# Carte_Barriere_Optique_Interface.net
KiCad netlist of a schematic drawn in Altium Designer
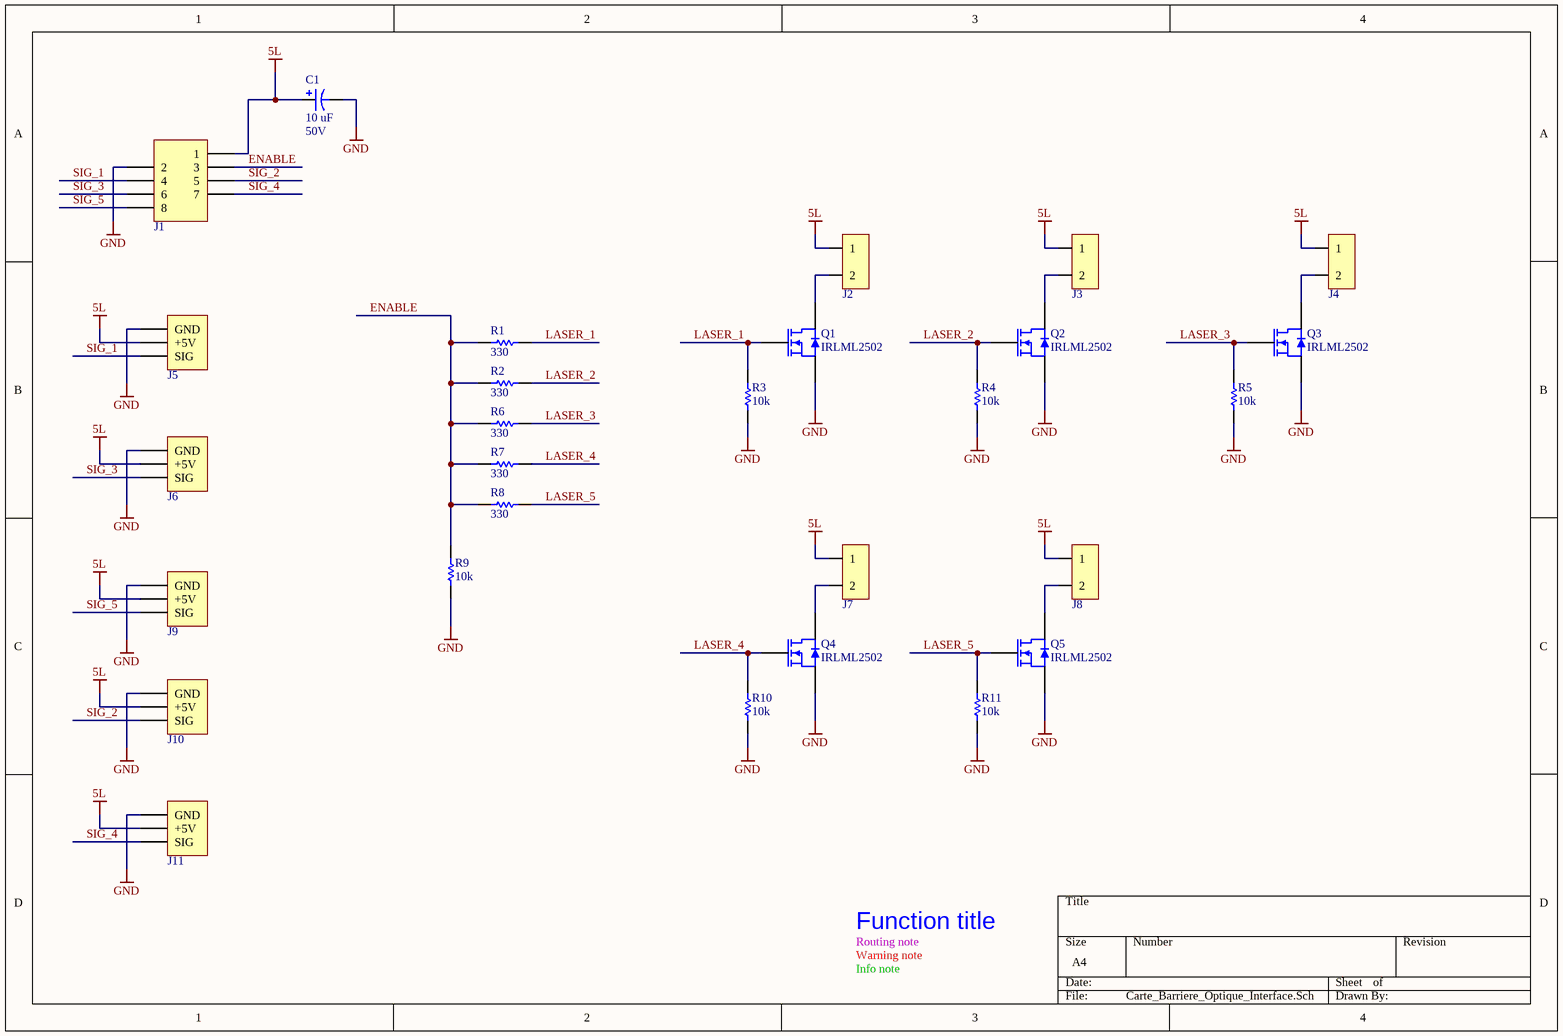
[diagram p0: Carte_Barriere_Optique_Interface.SchDoc]

(export (version "E")
  (design (tool "Eeschema 10.0.6"))
  (components
    (comp (ref "C1")
      (value "10 uF")
      (footprint "WCAP-ATG8_5x11x2x0.5")
      (description "CAP Alu 10 UF 20% 50 V")
      (fields
        (field (name "MANUFACTURER") "Wurth Elektronik")
        (field (name "MANUFACTURER PART NUMBER") "860010672009")
        (field (name "RATEDVOLTAGE") "50V")
      )
      (libsource (lib "Condensateur") (part "WCAP-ATG8, 860010672009"))
    )
    (comp (ref "J1")
      (value "690367280876")
      (footprint "690367280876")
      (description "WR-MM 8p Female SMT Connector with Polarization")
      (fields (field (name "MANUFACTURER") "Wurth Electronics Inc."))
      (libsource (lib "Connecteurs") (part "690367280876"))
    )
    (comp (ref "J2")
      (value "22-03-2021")
      (footprint "22-03-2021")
      (libsource (lib "Connecteurs") (part "22-03-2021"))
    )
    (comp (ref "J3")
      (value "22-03-2021")
      (footprint "22-03-2021")
      (libsource (lib "Connecteurs") (part "22-03-2021"))
    )
    (comp (ref "J4")
      (value "22-03-2021")
      (footprint "22-03-2021")
      (libsource (lib "Connecteurs") (part "22-03-2021"))
    )
    (comp (ref "J5")
      (value "61300311021")
      (footprint "61300311021")
      (description "CONN HEADER 3p horiz. 2.54mm")
      (fields (field (name "MANUFACTURER") "Wurth Electronics Inc."))
      (libsource (lib "Connecteurs") (part "61300311021"))
    )
    (comp (ref "J6")
      (value "61300311021")
      (footprint "61300311021")
      (description "CONN HEADER 3p horiz. 2.54mm")
      (fields (field (name "MANUFACTURER") "Wurth Electronics Inc."))
      (libsource (lib "Connecteurs") (part "61300311021"))
    )
    (comp (ref "J7")
      (value "22-03-2021")
      (footprint "22-03-2021")
      (libsource (lib "Connecteurs") (part "22-03-2021"))
    )
    (comp (ref "J8")
      (value "22-03-2021")
      (footprint "22-03-2021")
      (libsource (lib "Connecteurs") (part "22-03-2021"))
    )
    (comp (ref "J9")
      (value "61300311021")
      (footprint "61300311021")
      (description "CONN HEADER 3p horiz. 2.54mm")
      (fields (field (name "MANUFACTURER") "Wurth Electronics Inc."))
      (libsource (lib "Connecteurs") (part "61300311021"))
    )
    (comp (ref "J10")
      (value "61300311021")
      (footprint "61300311021")
      (description "CONN HEADER 3p horiz. 2.54mm")
      (fields (field (name "MANUFACTURER") "Wurth Electronics Inc."))
      (libsource (lib "Connecteurs") (part "61300311021"))
    )
    (comp (ref "J11")
      (value "61300311021")
      (footprint "61300311021")
      (description "CONN HEADER 3p horiz. 2.54mm")
      (fields (field (name "MANUFACTURER") "Wurth Electronics Inc."))
      (libsource (lib "Connecteurs") (part "61300311021"))
    )
    (comp (ref "Q1")
      (value "IRLML2502")
      (footprint "SOT-23")
      (description "MOSFET CANAL N SOT-23")
      (fields (field (name "MANUFACTURER PART NUMBER") "IRLML2502PBF"))
      (libsource (lib "Transistors") (part "IRLML2502"))
    )
    (comp (ref "Q2")
      (value "IRLML2502")
      (footprint "SOT-23")
      (description "MOSFET CANAL N SOT-23")
      (fields (field (name "MANUFACTURER PART NUMBER") "IRLML2502PBF"))
      (libsource (lib "Transistors") (part "IRLML2502"))
    )
    (comp (ref "Q3")
      (value "IRLML2502")
      (footprint "SOT-23")
      (description "MOSFET CANAL N SOT-23")
      (fields (field (name "MANUFACTURER PART NUMBER") "IRLML2502PBF"))
      (libsource (lib "Transistors") (part "IRLML2502"))
    )
    (comp (ref "Q4")
      (value "IRLML2502")
      (footprint "SOT-23")
      (description "MOSFET CANAL N SOT-23")
      (fields (field (name "MANUFACTURER PART NUMBER") "IRLML2502PBF"))
      (libsource (lib "Transistors") (part "IRLML2502"))
    )
    (comp (ref "Q5")
      (value "IRLML2502")
      (footprint "SOT-23")
      (description "MOSFET CANAL N SOT-23")
      (fields (field (name "MANUFACTURER PART NUMBER") "IRLML2502PBF"))
      (libsource (lib "Transistors") (part "IRLML2502"))
    )
    (comp (ref "R1")
      (value "330")
      (footprint "RESC1608X06N")
      (description "RES SMD 330 OHM 1% 1/10W 0603")
      (fields
        (field (name "MANUFACTURER") "Yageo")
        (field (name "MANUFACTURER PART NUMBER") "RC0603FR-07330RL")
      )
      (libsource (lib "Resistance") (part "RC0603FR-07330RL"))
    )
    (comp (ref "R2")
      (value "330")
      (footprint "RESC1608X06N")
      (description "RES SMD 330 OHM 1% 1/10W 0603")
      (fields
        (field (name "MANUFACTURER") "Yageo")
        (field (name "MANUFACTURER PART NUMBER") "RC0603FR-07330RL")
      )
      (libsource (lib "Resistance") (part "RC0603FR-07330RL"))
    )
    (comp (ref "R3")
      (value "10k")
      (footprint "RESC1608X06N")
      (description "RES SMD 10K OHM 1% 1/10W 0603")
      (fields
        (field (name "MANUFACTURER") "Yageo")
        (field (name "MANUFACTURER PART NUMBER") "RC0603FR-0710KL")
      )
      (libsource (lib "Resistance") (part "RC0603FR-0710KL"))
    )
    (comp (ref "R4")
      (value "10k")
      (footprint "RESC1608X06N")
      (description "RES SMD 10K OHM 1% 1/10W 0603")
      (fields
        (field (name "MANUFACTURER") "Yageo")
        (field (name "MANUFACTURER PART NUMBER") "RC0603FR-0710KL")
      )
      (libsource (lib "Resistance") (part "RC0603FR-0710KL"))
    )
    (comp (ref "R5")
      (value "10k")
      (footprint "RESC1608X06N")
      (description "RES SMD 10K OHM 1% 1/10W 0603")
      (fields
        (field (name "MANUFACTURER") "Yageo")
        (field (name "MANUFACTURER PART NUMBER") "RC0603FR-0710KL")
      )
      (libsource (lib "Resistance") (part "RC0603FR-0710KL"))
    )
    (comp (ref "R6")
      (value "330")
      (footprint "RESC1608X06N")
      (description "RES SMD 330 OHM 1% 1/10W 0603")
      (fields
        (field (name "MANUFACTURER") "Yageo")
        (field (name "MANUFACTURER PART NUMBER") "RC0603FR-07330RL")
      )
      (libsource (lib "Resistance") (part "RC0603FR-07330RL"))
    )
    (comp (ref "R7")
      (value "330")
      (footprint "RESC1608X06N")
      (description "RES SMD 330 OHM 1% 1/10W 0603")
      (fields
        (field (name "MANUFACTURER") "Yageo")
        (field (name "MANUFACTURER PART NUMBER") "RC0603FR-07330RL")
      )
      (libsource (lib "Resistance") (part "RC0603FR-07330RL"))
    )
    (comp (ref "R8")
      (value "330")
      (footprint "RESC1608X06N")
      (description "RES SMD 330 OHM 1% 1/10W 0603")
      (fields
        (field (name "MANUFACTURER") "Yageo")
        (field (name "MANUFACTURER PART NUMBER") "RC0603FR-07330RL")
      )
      (libsource (lib "Resistance") (part "RC0603FR-07330RL"))
    )
    (comp (ref "R9")
      (value "10k")
      (footprint "RESC1608X06N")
      (description "RES SMD 10K OHM 1% 1/10W 0603")
      (fields
        (field (name "MANUFACTURER") "Yageo")
        (field (name "MANUFACTURER PART NUMBER") "RC0603FR-0710KL")
      )
      (libsource (lib "Resistance") (part "RC0603FR-0710KL"))
    )
    (comp (ref "R10")
      (value "10k")
      (footprint "RESC1608X06N")
      (description "RES SMD 10K OHM 1% 1/10W 0603")
      (fields
        (field (name "MANUFACTURER") "Yageo")
        (field (name "MANUFACTURER PART NUMBER") "RC0603FR-0710KL")
      )
      (libsource (lib "Resistance") (part "RC0603FR-0710KL"))
    )
    (comp (ref "R11")
      (value "10k")
      (footprint "RESC1608X06N")
      (description "RES SMD 10K OHM 1% 1/10W 0603")
      (fields
        (field (name "MANUFACTURER") "Yageo")
        (field (name "MANUFACTURER PART NUMBER") "RC0603FR-0710KL")
      )
      (libsource (lib "Resistance") (part "RC0603FR-0710KL"))
    )
  )
  (nets
    (net (code "1") (name "/ENABLE") (class "Default")
      (node (ref "J1") (pin "3") (pinfunction "3_3") (pintype "passive"))
      (node (ref "R1") (pin "1") (pinfunction "1_1") (pintype "passive"))
      (node (ref "R2") (pin "1") (pinfunction "1_1") (pintype "passive"))
      (node (ref "R6") (pin "1") (pinfunction "1_1") (pintype "passive"))
      (node (ref "R7") (pin "1") (pinfunction "1_1") (pintype "passive"))
      (node (ref "R8") (pin "1") (pinfunction "1_1") (pintype "passive"))
      (node (ref "R9") (pin "2") (pinfunction "2_2") (pintype "passive"))
    )
    (net (code "2") (name "/LASER_1") (class "Default")
      (node (ref "Q1") (pin "1") (pinfunction "G_1") (pintype "passive"))
      (node (ref "R1") (pin "2") (pinfunction "2_2") (pintype "passive"))
      (node (ref "R3") (pin "2") (pinfunction "2_2") (pintype "passive"))
    )
    (net (code "3") (name "/LASER_2") (class "Default")
      (node (ref "Q2") (pin "1") (pinfunction "G_1") (pintype "passive"))
      (node (ref "R2") (pin "2") (pinfunction "2_2") (pintype "passive"))
      (node (ref "R4") (pin "2") (pinfunction "2_2") (pintype "passive"))
    )
    (net (code "4") (name "/LASER_3") (class "Default")
      (node (ref "Q3") (pin "1") (pinfunction "G_1") (pintype "passive"))
      (node (ref "R5") (pin "2") (pinfunction "2_2") (pintype "passive"))
      (node (ref "R6") (pin "2") (pinfunction "2_2") (pintype "passive"))
    )
    (net (code "5") (name "/LASER_4") (class "Default")
      (node (ref "Q4") (pin "1") (pinfunction "G_1") (pintype "passive"))
      (node (ref "R10") (pin "2") (pinfunction "2_2") (pintype "passive"))
      (node (ref "R7") (pin "2") (pinfunction "2_2") (pintype "passive"))
    )
    (net (code "6") (name "/LASER_5") (class "Default")
      (node (ref "Q5") (pin "1") (pinfunction "G_1") (pintype "passive"))
      (node (ref "R11") (pin "2") (pinfunction "2_2") (pintype "passive"))
      (node (ref "R8") (pin "2") (pinfunction "2_2") (pintype "passive"))
    )
    (net (code "7") (name "/SIG_1") (class "Default")
      (node (ref "J1") (pin "4") (pinfunction "4_4") (pintype "passive"))
      (node (ref "J5") (pin "3") (pinfunction "SIG_3") (pintype "passive"))
    )
    (net (code "8") (name "/SIG_2") (class "Default")
      (node (ref "J1") (pin "5") (pinfunction "5_5") (pintype "passive"))
      (node (ref "J10") (pin "3") (pinfunction "SIG_3") (pintype "passive"))
    )
    (net (code "9") (name "/SIG_3") (class "Default")
      (node (ref "J1") (pin "6") (pinfunction "6_6") (pintype "passive"))
      (node (ref "J6") (pin "3") (pinfunction "SIG_3") (pintype "passive"))
    )
    (net (code "10") (name "/SIG_4") (class "Default")
      (node (ref "J1") (pin "7") (pinfunction "7_7") (pintype "passive"))
      (node (ref "J11") (pin "3") (pinfunction "SIG_3") (pintype "passive"))
    )
    (net (code "11") (name "/SIG_5") (class "Default")
      (node (ref "J1") (pin "8") (pinfunction "8_8") (pintype "passive"))
      (node (ref "J9") (pin "3") (pinfunction "SIG_3") (pintype "passive"))
    )
    (net (code "12") (name "5L") (class "Default")
      (node (ref "C1") (pin "1") (pinfunction "1_1") (pintype "passive"))
      (node (ref "J1") (pin "1") (pinfunction "1_1") (pintype "passive"))
      (node (ref "J10") (pin "2") (pinfunction "+5V_2") (pintype "passive"))
      (node (ref "J11") (pin "2") (pinfunction "+5V_2") (pintype "passive"))
      (node (ref "J2") (pin "1") (pinfunction "1_1") (pintype "passive"))
      (node (ref "J3") (pin "1") (pinfunction "1_1") (pintype "passive"))
      (node (ref "J4") (pin "1") (pinfunction "1_1") (pintype "passive"))
      (node (ref "J5") (pin "2") (pinfunction "+5V_2") (pintype "passive"))
      (node (ref "J6") (pin "2") (pinfunction "+5V_2") (pintype "passive"))
      (node (ref "J7") (pin "1") (pinfunction "1_1") (pintype "passive"))
      (node (ref "J8") (pin "1") (pinfunction "1_1") (pintype "passive"))
      (node (ref "J9") (pin "2") (pinfunction "+5V_2") (pintype "passive"))
    )
    (net (code "13") (name "GND") (class "Default")
      (node (ref "C1") (pin "2") (pinfunction "2_2") (pintype "passive"))
      (node (ref "J1") (pin "2") (pinfunction "2_2") (pintype "passive"))
      (node (ref "J10") (pin "1") (pinfunction "GND_1") (pintype "passive"))
      (node (ref "J11") (pin "1") (pinfunction "GND_1") (pintype "passive"))
      (node (ref "J5") (pin "1") (pinfunction "GND_1") (pintype "passive"))
      (node (ref "J6") (pin "1") (pinfunction "GND_1") (pintype "passive"))
      (node (ref "J9") (pin "1") (pinfunction "GND_1") (pintype "passive"))
      (node (ref "Q1") (pin "2") (pinfunction "S_2") (pintype "passive"))
      (node (ref "Q2") (pin "2") (pinfunction "S_2") (pintype "passive"))
      (node (ref "Q3") (pin "2") (pinfunction "S_2") (pintype "passive"))
      (node (ref "Q4") (pin "2") (pinfunction "S_2") (pintype "passive"))
      (node (ref "Q5") (pin "2") (pinfunction "S_2") (pintype "passive"))
      (node (ref "R10") (pin "1") (pinfunction "1_1") (pintype "passive"))
      (node (ref "R11") (pin "1") (pinfunction "1_1") (pintype "passive"))
      (node (ref "R3") (pin "1") (pinfunction "1_1") (pintype "passive"))
      (node (ref "R4") (pin "1") (pinfunction "1_1") (pintype "passive"))
      (node (ref "R5") (pin "1") (pinfunction "1_1") (pintype "passive"))
      (node (ref "R9") (pin "1") (pinfunction "1_1") (pintype "passive"))
    )
    (net (code "14") (name "Net-(Q1-D)") (class "Default")
      (node (ref "J2") (pin "2") (pinfunction "2_2") (pintype "passive"))
      (node (ref "Q1") (pin "3") (pinfunction "D_3") (pintype "passive"))
    )
    (net (code "15") (name "Net-(Q2-D)") (class "Default")
      (node (ref "J3") (pin "2") (pinfunction "2_2") (pintype "passive"))
      (node (ref "Q2") (pin "3") (pinfunction "D_3") (pintype "passive"))
    )
    (net (code "16") (name "Net-(Q3-D)") (class "Default")
      (node (ref "J4") (pin "2") (pinfunction "2_2") (pintype "passive"))
      (node (ref "Q3") (pin "3") (pinfunction "D_3") (pintype "passive"))
    )
    (net (code "17") (name "Net-(Q4-D)") (class "Default")
      (node (ref "J7") (pin "2") (pinfunction "2_2") (pintype "passive"))
      (node (ref "Q4") (pin "3") (pinfunction "D_3") (pintype "passive"))
    )
    (net (code "18") (name "Net-(Q5-D)") (class "Default")
      (node (ref "J8") (pin "2") (pinfunction "2_2") (pintype "passive"))
      (node (ref "Q5") (pin "3") (pinfunction "D_3") (pintype "passive"))
    )
  )
)
